# 04_RV1126B_Core_Board.net
KiCad netlist of a schematic drawn in Altium Designer
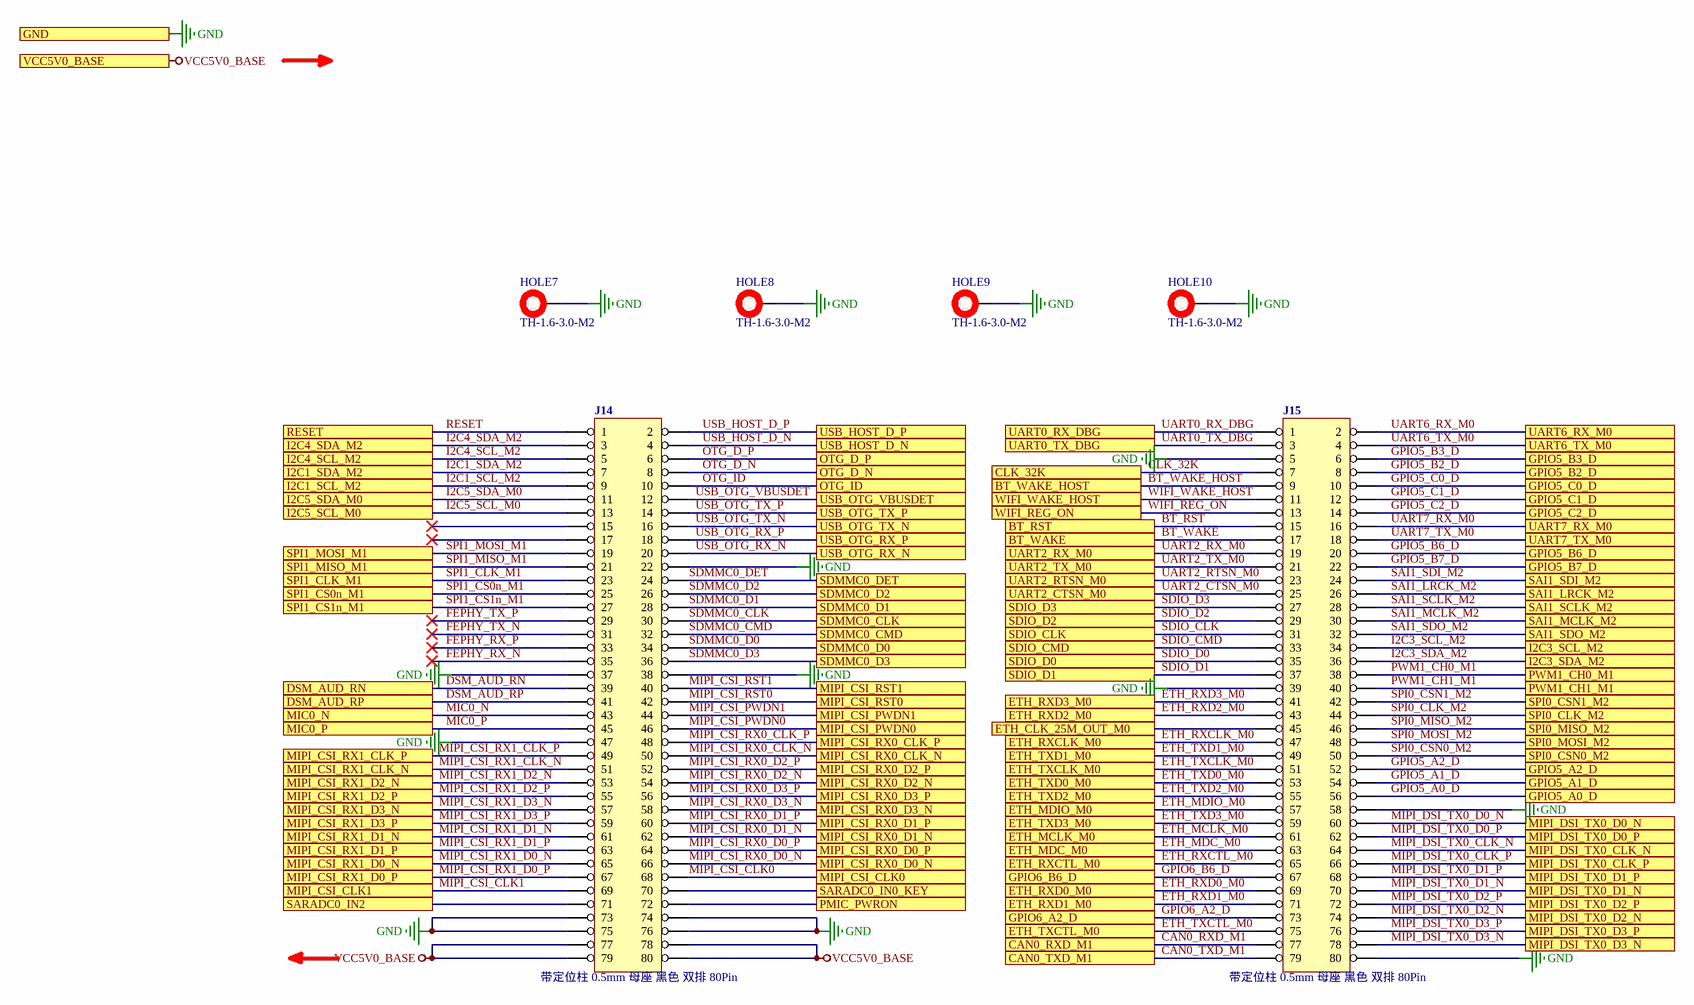
[diagram p0: 04.RV1126B_Core_Board.SchDoc]

(export (version "E")
  (design (tool "Eeschema 10.0.6"))
  (components
    (comp (ref "HOLE7")
      (value "TH-1.6-3.0-M2")
      (footprint "TH-1.6-3.0-M2")
      (description "SPZL000886")
      (fields (field (name "型号") "TH-1.6-3.0-M2"))
      (libsource (lib "Other_EASY-EAI") (part "螺柱 TH-1.6-3.0-M2"))
    )
    (comp (ref "HOLE8")
      (value "TH-1.6-3.0-M2")
      (footprint "TH-1.6-3.0-M2")
      (description "SPZL000886")
      (fields (field (name "型号") "TH-1.6-3.0-M2"))
      (libsource (lib "Other_EASY-EAI") (part "螺柱 TH-1.6-3.0-M2"))
    )
    (comp (ref "HOLE9")
      (value "TH-1.6-3.0-M2")
      (footprint "TH-1.6-3.0-M2")
      (description "SPZL000886")
      (fields (field (name "型号") "TH-1.6-3.0-M2"))
      (libsource (lib "Other_EASY-EAI") (part "螺柱 TH-1.6-3.0-M2"))
    )
    (comp (ref "HOLE10")
      (value "TH-1.6-3.0-M2")
      (footprint "TH-1.6-3.0-M2")
      (description "SPZL000886")
      (fields (field (name "型号") "TH-1.6-3.0-M2"))
      (libsource (lib "Other_EASY-EAI") (part "螺柱 TH-1.6-3.0-M2"))
    )
    (comp (ref "J14")
      (value "DF12NA(3.0)-80DP-0.5V(51)")
      (footprint "CONN-SMD_80P-P0.50_DF12NA-3.0-80DP-0.5V")
      (description "SPZL000772")
      (fields (field (name "描述") "带定位柱 0.5mm 母座 黑色 双排 80Pin"))
      (libsource (lib "Connector_EASY-EAI") (part "DF12NA(3.0)-80DP-0.5V(51)"))
    )
    (comp (ref "J15")
      (value "DF12NA(3.0)-80DP-0.5V(51)")
      (footprint "CONN-SMD_80P-P0.50_DF12NA-3.0-80DP-0.5V")
      (description "SPZL000772")
      (fields (field (name "描述") "带定位柱 0.5mm 母座 黑色 双排 80Pin"))
      (libsource (lib "Connector_EASY-EAI") (part "DF12NA(3.0)-80DP-0.5V(51)"))
    )
  )
  (nets
    (net (code "1") (name "/BT_RST") (class "Default")
      (node (ref "J15") (pin "15") (pinfunction "15_15") (pintype "passive"))
    )
    (net (code "2") (name "/BT_WAKE") (class "Default")
      (node (ref "J15") (pin "17") (pinfunction "17_17") (pintype "passive"))
    )
    (net (code "3") (name "/BT_WAKE_HOST") (class "Default")
      (node (ref "J15") (pin "9") (pinfunction "9_9") (pintype "passive"))
    )
    (net (code "4") (name "/CAN0_RXD_M1") (class "Default")
      (node (ref "J15") (pin "77") (pinfunction "77_77") (pintype "passive"))
    )
    (net (code "5") (name "/CAN0_TXD_M1") (class "Default")
      (node (ref "J15") (pin "79") (pinfunction "79_79") (pintype "passive"))
    )
    (net (code "6") (name "/CLK_32K") (class "Default")
      (node (ref "J15") (pin "7") (pinfunction "7_7") (pintype "passive"))
    )
    (net (code "7") (name "/DSM_AUD_RN") (class "Default")
      (node (ref "J14") (pin "39") (pinfunction "39_39") (pintype "passive"))
    )
    (net (code "8") (name "/DSM_AUD_RP") (class "Default")
      (node (ref "J14") (pin "41") (pinfunction "41_41") (pintype "passive"))
    )
    (net (code "9") (name "/ETH_CLK_25M_OUT_M0") (class "Default")
      (node (ref "J15") (pin "45") (pinfunction "45_45") (pintype "passive"))
    )
    (net (code "10") (name "/ETH_MCLK_M0") (class "Default")
      (node (ref "J15") (pin "61") (pinfunction "61_61") (pintype "passive"))
    )
    (net (code "11") (name "/ETH_MDC_M0") (class "Default")
      (node (ref "J15") (pin "63") (pinfunction "63_63") (pintype "passive"))
    )
    (net (code "12") (name "/ETH_MDIO_M0") (class "Default")
      (node (ref "J15") (pin "57") (pinfunction "57_57") (pintype "passive"))
    )
    (net (code "13") (name "/ETH_RXCLK_M0") (class "Default")
      (node (ref "J15") (pin "47") (pinfunction "47_47") (pintype "passive"))
    )
    (net (code "14") (name "/ETH_RXCTL_M0") (class "Default")
      (node (ref "J15") (pin "65") (pinfunction "65_65") (pintype "passive"))
    )
    (net (code "15") (name "/ETH_RXD0_M0") (class "Default")
      (node (ref "J15") (pin "69") (pinfunction "69_69") (pintype "passive"))
    )
    (net (code "16") (name "/ETH_RXD1_M0") (class "Default")
      (node (ref "J15") (pin "71") (pinfunction "71_71") (pintype "passive"))
    )
    (net (code "17") (name "/ETH_RXD2_M0") (class "Default")
      (node (ref "J15") (pin "43") (pinfunction "43_43") (pintype "passive"))
    )
    (net (code "18") (name "/ETH_RXD3_M0") (class "Default")
      (node (ref "J15") (pin "41") (pinfunction "41_41") (pintype "passive"))
    )
    (net (code "19") (name "/ETH_TXCLK_M0") (class "Default")
      (node (ref "J15") (pin "51") (pinfunction "51_51") (pintype "passive"))
    )
    (net (code "20") (name "/ETH_TXCTL_M0") (class "Default")
      (node (ref "J15") (pin "75") (pinfunction "75_75") (pintype "passive"))
    )
    (net (code "21") (name "/ETH_TXD0_M0") (class "Default")
      (node (ref "J15") (pin "53") (pinfunction "53_53") (pintype "passive"))
    )
    (net (code "22") (name "/ETH_TXD1_M0") (class "Default")
      (node (ref "J15") (pin "49") (pinfunction "49_49") (pintype "passive"))
    )
    (net (code "23") (name "/ETH_TXD2_M0") (class "Default")
      (node (ref "J15") (pin "55") (pinfunction "55_55") (pintype "passive"))
    )
    (net (code "24") (name "/ETH_TXD3_M0") (class "Default")
      (node (ref "J15") (pin "59") (pinfunction "59_59") (pintype "passive"))
    )
    (net (code "25") (name "/FEPHY_RX_N") (class "Default")
      (node (ref "J14") (pin "35") (pinfunction "35_35") (pintype "passive+no_connect"))
    )
    (net (code "26") (name "/FEPHY_RX_P") (class "Default")
      (node (ref "J14") (pin "33") (pinfunction "33_33") (pintype "passive+no_connect"))
    )
    (net (code "27") (name "/FEPHY_TX_N") (class "Default")
      (node (ref "J14") (pin "31") (pinfunction "31_31") (pintype "passive+no_connect"))
    )
    (net (code "28") (name "/FEPHY_TX_P") (class "Default")
      (node (ref "J14") (pin "29") (pinfunction "29_29") (pintype "passive+no_connect"))
    )
    (net (code "29") (name "/GPIO5_A0_D") (class "Default")
      (node (ref "J15") (pin "56") (pinfunction "56_56") (pintype "passive"))
    )
    (net (code "30") (name "/GPIO5_A1_D") (class "Default")
      (node (ref "J15") (pin "54") (pinfunction "54_54") (pintype "passive"))
    )
    (net (code "31") (name "/GPIO5_A2_D") (class "Default")
      (node (ref "J15") (pin "52") (pinfunction "52_52") (pintype "passive"))
    )
    (net (code "32") (name "/GPIO5_B2_D") (class "Default")
      (node (ref "J15") (pin "8") (pinfunction "8_8") (pintype "passive"))
    )
    (net (code "33") (name "/GPIO5_B3_D") (class "Default")
      (node (ref "J15") (pin "6") (pinfunction "6_6") (pintype "passive"))
    )
    (net (code "34") (name "/GPIO5_B6_D") (class "Default")
      (node (ref "J15") (pin "20") (pinfunction "20_20") (pintype "passive"))
    )
    (net (code "35") (name "/GPIO5_B7_D") (class "Default")
      (node (ref "J15") (pin "22") (pinfunction "22_22") (pintype "passive"))
    )
    (net (code "36") (name "/GPIO5_C0_D") (class "Default")
      (node (ref "J15") (pin "10") (pinfunction "10_10") (pintype "passive"))
    )
    (net (code "37") (name "/GPIO5_C1_D") (class "Default")
      (node (ref "J15") (pin "12") (pinfunction "12_12") (pintype "passive"))
    )
    (net (code "38") (name "/GPIO5_C2_D") (class "Default")
      (node (ref "J15") (pin "14") (pinfunction "14_14") (pintype "passive"))
    )
    (net (code "39") (name "/GPIO6_A2_D") (class "Default")
      (node (ref "J15") (pin "73") (pinfunction "73_73") (pintype "passive"))
    )
    (net (code "40") (name "/GPIO6_B6_D") (class "Default")
      (node (ref "J15") (pin "67") (pinfunction "67_67") (pintype "passive"))
    )
    (net (code "41") (name "/I2C1_SCL_M2") (class "Default")
      (node (ref "J14") (pin "9") (pinfunction "9_9") (pintype "passive"))
    )
    (net (code "42") (name "/I2C1_SDA_M2") (class "Default")
      (node (ref "J14") (pin "7") (pinfunction "7_7") (pintype "passive"))
    )
    (net (code "43") (name "/I2C3_SCL_M2") (class "Default")
      (node (ref "J15") (pin "34") (pinfunction "34_34") (pintype "passive"))
    )
    (net (code "44") (name "/I2C3_SDA_M2") (class "Default")
      (node (ref "J15") (pin "36") (pinfunction "36_36") (pintype "passive"))
    )
    (net (code "45") (name "/I2C4_SCL_M2") (class "Default")
      (node (ref "J14") (pin "5") (pinfunction "5_5") (pintype "passive"))
    )
    (net (code "46") (name "/I2C4_SDA_M2") (class "Default")
      (node (ref "J14") (pin "3") (pinfunction "3_3") (pintype "passive"))
    )
    (net (code "47") (name "/I2C5_SCL_M0") (class "Default")
      (node (ref "J14") (pin "13") (pinfunction "13_13") (pintype "passive"))
    )
    (net (code "48") (name "/I2C5_SDA_M0") (class "Default")
      (node (ref "J14") (pin "11") (pinfunction "11_11") (pintype "passive"))
    )
    (net (code "49") (name "/MIC0_N") (class "Default")
      (node (ref "J14") (pin "43") (pinfunction "43_43") (pintype "passive"))
    )
    (net (code "50") (name "/MIC0_P") (class "Default")
      (node (ref "J14") (pin "45") (pinfunction "45_45") (pintype "passive"))
    )
    (net (code "51") (name "/MIPI_CSI_CLK0") (class "Default")
      (node (ref "J14") (pin "68") (pinfunction "68_68") (pintype "passive"))
    )
    (net (code "52") (name "/MIPI_CSI_CLK1") (class "Default")
      (node (ref "J14") (pin "69") (pinfunction "69_69") (pintype "passive"))
    )
    (net (code "53") (name "/MIPI_CSI_PWDN0") (class "Default")
      (node (ref "J14") (pin "46") (pinfunction "46_46") (pintype "passive"))
    )
    (net (code "54") (name "/MIPI_CSI_PWDN1") (class "Default")
      (node (ref "J14") (pin "44") (pinfunction "44_44") (pintype "passive"))
    )
    (net (code "55") (name "/MIPI_CSI_RST0") (class "Default")
      (node (ref "J14") (pin "42") (pinfunction "42_42") (pintype "passive"))
    )
    (net (code "56") (name "/MIPI_CSI_RST1") (class "Default")
      (node (ref "J14") (pin "40") (pinfunction "40_40") (pintype "passive"))
    )
    (net (code "57") (name "/MIPI_CSI_RX0_CLK_N") (class "Default")
      (node (ref "J14") (pin "50") (pinfunction "50_50") (pintype "passive"))
    )
    (net (code "58") (name "/MIPI_CSI_RX0_CLK_P") (class "Default")
      (node (ref "J14") (pin "48") (pinfunction "48_48") (pintype "passive"))
    )
    (net (code "59") (name "/MIPI_CSI_RX0_D0_N") (class "Default")
      (node (ref "J14") (pin "66") (pinfunction "66_66") (pintype "passive"))
    )
    (net (code "60") (name "/MIPI_CSI_RX0_D0_P") (class "Default")
      (node (ref "J14") (pin "64") (pinfunction "64_64") (pintype "passive"))
    )
    (net (code "61") (name "/MIPI_CSI_RX0_D1_N") (class "Default")
      (node (ref "J14") (pin "62") (pinfunction "62_62") (pintype "passive"))
    )
    (net (code "62") (name "/MIPI_CSI_RX0_D1_P") (class "Default")
      (node (ref "J14") (pin "60") (pinfunction "60_60") (pintype "passive"))
    )
    (net (code "63") (name "/MIPI_CSI_RX0_D2_N") (class "Default")
      (node (ref "J14") (pin "54") (pinfunction "54_54") (pintype "passive"))
    )
    (net (code "64") (name "/MIPI_CSI_RX0_D2_P") (class "Default")
      (node (ref "J14") (pin "52") (pinfunction "52_52") (pintype "passive"))
    )
    (net (code "65") (name "/MIPI_CSI_RX0_D3_N") (class "Default")
      (node (ref "J14") (pin "58") (pinfunction "58_58") (pintype "passive"))
    )
    (net (code "66") (name "/MIPI_CSI_RX0_D3_P") (class "Default")
      (node (ref "J14") (pin "56") (pinfunction "56_56") (pintype "passive"))
    )
    (net (code "67") (name "/MIPI_CSI_RX1_CLK_N") (class "Default")
      (node (ref "J14") (pin "51") (pinfunction "51_51") (pintype "passive"))
    )
    (net (code "68") (name "/MIPI_CSI_RX1_CLK_P") (class "Default")
      (node (ref "J14") (pin "49") (pinfunction "49_49") (pintype "passive"))
    )
    (net (code "69") (name "/MIPI_CSI_RX1_D0_N") (class "Default")
      (node (ref "J14") (pin "65") (pinfunction "65_65") (pintype "passive"))
    )
    (net (code "70") (name "/MIPI_CSI_RX1_D0_P") (class "Default")
      (node (ref "J14") (pin "67") (pinfunction "67_67") (pintype "passive"))
    )
    (net (code "71") (name "/MIPI_CSI_RX1_D1_N") (class "Default")
      (node (ref "J14") (pin "61") (pinfunction "61_61") (pintype "passive"))
    )
    (net (code "72") (name "/MIPI_CSI_RX1_D1_P") (class "Default")
      (node (ref "J14") (pin "63") (pinfunction "63_63") (pintype "passive"))
    )
    (net (code "73") (name "/MIPI_CSI_RX1_D2_N") (class "Default")
      (node (ref "J14") (pin "53") (pinfunction "53_53") (pintype "passive"))
    )
    (net (code "74") (name "/MIPI_CSI_RX1_D2_P") (class "Default")
      (node (ref "J14") (pin "55") (pinfunction "55_55") (pintype "passive"))
    )
    (net (code "75") (name "/MIPI_CSI_RX1_D3_N") (class "Default")
      (node (ref "J14") (pin "57") (pinfunction "57_57") (pintype "passive"))
    )
    (net (code "76") (name "/MIPI_CSI_RX1_D3_P") (class "Default")
      (node (ref "J14") (pin "59") (pinfunction "59_59") (pintype "passive"))
    )
    (net (code "77") (name "/MIPI_DSI_TX0_CLK_N") (class "Default")
      (node (ref "J15") (pin "64") (pinfunction "64_64") (pintype "passive"))
    )
    (net (code "78") (name "/MIPI_DSI_TX0_CLK_P") (class "Default")
      (node (ref "J15") (pin "66") (pinfunction "66_66") (pintype "passive"))
    )
    (net (code "79") (name "/MIPI_DSI_TX0_D0_N") (class "Default")
      (node (ref "J15") (pin "60") (pinfunction "60_60") (pintype "passive"))
    )
    (net (code "80") (name "/MIPI_DSI_TX0_D0_P") (class "Default")
      (node (ref "J15") (pin "62") (pinfunction "62_62") (pintype "passive"))
    )
    (net (code "81") (name "/MIPI_DSI_TX0_D1_N") (class "Default")
      (node (ref "J15") (pin "70") (pinfunction "70_70") (pintype "passive"))
    )
    (net (code "82") (name "/MIPI_DSI_TX0_D1_P") (class "Default")
      (node (ref "J15") (pin "68") (pinfunction "68_68") (pintype "passive"))
    )
    (net (code "83") (name "/MIPI_DSI_TX0_D2_N") (class "Default")
      (node (ref "J15") (pin "74") (pinfunction "74_74") (pintype "passive"))
    )
    (net (code "84") (name "/MIPI_DSI_TX0_D2_P") (class "Default")
      (node (ref "J15") (pin "72") (pinfunction "72_72") (pintype "passive"))
    )
    (net (code "85") (name "/MIPI_DSI_TX0_D3_N") (class "Default")
      (node (ref "J15") (pin "78") (pinfunction "78_78") (pintype "passive"))
    )
    (net (code "86") (name "/MIPI_DSI_TX0_D3_P") (class "Default")
      (node (ref "J15") (pin "76") (pinfunction "76_76") (pintype "passive"))
    )
    (net (code "87") (name "/OTG_D_N") (class "Default")
      (node (ref "J14") (pin "8") (pinfunction "8_8") (pintype "passive"))
    )
    (net (code "88") (name "/OTG_D_P") (class "Default")
      (node (ref "J14") (pin "6") (pinfunction "6_6") (pintype "passive"))
    )
    (net (code "89") (name "/OTG_ID") (class "Default")
      (node (ref "J14") (pin "10") (pinfunction "10_10") (pintype "passive"))
    )
    (net (code "90") (name "/PMIC_PWRON") (class "Default")
      (node (ref "J14") (pin "72") (pinfunction "72_72") (pintype "passive"))
    )
    (net (code "91") (name "/PWM1_CH0_M1") (class "Default")
      (node (ref "J15") (pin "38") (pinfunction "38_38") (pintype "passive"))
    )
    (net (code "92") (name "/PWM1_CH1_M1") (class "Default")
      (node (ref "J15") (pin "40") (pinfunction "40_40") (pintype "passive"))
    )
    (net (code "93") (name "/RESET") (class "Default")
      (node (ref "J14") (pin "1") (pinfunction "1_1") (pintype "passive"))
    )
    (net (code "94") (name "/SAI1_LRCK_M2") (class "Default")
      (node (ref "J15") (pin "26") (pinfunction "26_26") (pintype "passive"))
    )
    (net (code "95") (name "/SAI1_MCLK_M2") (class "Default")
      (node (ref "J15") (pin "30") (pinfunction "30_30") (pintype "passive"))
    )
    (net (code "96") (name "/SAI1_SCLK_M2") (class "Default")
      (node (ref "J15") (pin "28") (pinfunction "28_28") (pintype "passive"))
    )
    (net (code "97") (name "/SAI1_SDI_M2") (class "Default")
      (node (ref "J15") (pin "24") (pinfunction "24_24") (pintype "passive"))
    )
    (net (code "98") (name "/SAI1_SDO_M2") (class "Default")
      (node (ref "J15") (pin "32") (pinfunction "32_32") (pintype "passive"))
    )
    (net (code "99") (name "/SARADC0_IN0_KEY") (class "Default")
      (node (ref "J14") (pin "70") (pinfunction "70_70") (pintype "passive"))
    )
    (net (code "100") (name "/SARADC0_IN2") (class "Default")
      (node (ref "J14") (pin "71") (pinfunction "71_71") (pintype "passive"))
    )
    (net (code "101") (name "/SDIO_CLK") (class "Default")
      (node (ref "J15") (pin "31") (pinfunction "31_31") (pintype "passive"))
    )
    (net (code "102") (name "/SDIO_CMD") (class "Default")
      (node (ref "J15") (pin "33") (pinfunction "33_33") (pintype "passive"))
    )
    (net (code "103") (name "/SDIO_D0") (class "Default")
      (node (ref "J15") (pin "35") (pinfunction "35_35") (pintype "passive"))
    )
    (net (code "104") (name "/SDIO_D1") (class "Default")
      (node (ref "J15") (pin "37") (pinfunction "37_37") (pintype "passive"))
    )
    (net (code "105") (name "/SDIO_D2") (class "Default")
      (node (ref "J15") (pin "29") (pinfunction "29_29") (pintype "passive"))
    )
    (net (code "106") (name "/SDIO_D3") (class "Default")
      (node (ref "J15") (pin "27") (pinfunction "27_27") (pintype "passive"))
    )
    (net (code "107") (name "/SDMMC0_CLK") (class "Default")
      (node (ref "J14") (pin "30") (pinfunction "30_30") (pintype "passive"))
    )
    (net (code "108") (name "/SDMMC0_CMD") (class "Default")
      (node (ref "J14") (pin "32") (pinfunction "32_32") (pintype "passive"))
    )
    (net (code "109") (name "/SDMMC0_D0") (class "Default")
      (node (ref "J14") (pin "34") (pinfunction "34_34") (pintype "passive"))
    )
    (net (code "110") (name "/SDMMC0_D1") (class "Default")
      (node (ref "J14") (pin "28") (pinfunction "28_28") (pintype "passive"))
    )
    (net (code "111") (name "/SDMMC0_D2") (class "Default")
      (node (ref "J14") (pin "26") (pinfunction "26_26") (pintype "passive"))
    )
    (net (code "112") (name "/SDMMC0_D3") (class "Default")
      (node (ref "J14") (pin "36") (pinfunction "36_36") (pintype "passive"))
    )
    (net (code "113") (name "/SDMMC0_DET") (class "Default")
      (node (ref "J14") (pin "24") (pinfunction "24_24") (pintype "passive"))
    )
    (net (code "114") (name "/SPI0_CLK_M2") (class "Default")
      (node (ref "J15") (pin "44") (pinfunction "44_44") (pintype "passive"))
    )
    (net (code "115") (name "/SPI0_CSN0_M2") (class "Default")
      (node (ref "J15") (pin "50") (pinfunction "50_50") (pintype "passive"))
    )
    (net (code "116") (name "/SPI0_CSN1_M2") (class "Default")
      (node (ref "J15") (pin "42") (pinfunction "42_42") (pintype "passive"))
    )
    (net (code "117") (name "/SPI0_MISO_M2") (class "Default")
      (node (ref "J15") (pin "46") (pinfunction "46_46") (pintype "passive"))
    )
    (net (code "118") (name "/SPI0_MOSI_M2") (class "Default")
      (node (ref "J15") (pin "48") (pinfunction "48_48") (pintype "passive"))
    )
    (net (code "119") (name "/SPI1_CLK_M1") (class "Default")
      (node (ref "J14") (pin "23") (pinfunction "23_23") (pintype "passive"))
    )
    (net (code "120") (name "/SPI1_CS0n_M1") (class "Default")
      (node (ref "J14") (pin "25") (pinfunction "25_25") (pintype "passive"))
    )
    (net (code "121") (name "/SPI1_CS1n_M1") (class "Default")
      (node (ref "J14") (pin "27") (pinfunction "27_27") (pintype "passive"))
    )
    (net (code "122") (name "/SPI1_MISO_M1") (class "Default")
      (node (ref "J14") (pin "21") (pinfunction "21_21") (pintype "passive"))
    )
    (net (code "123") (name "/SPI1_MOSI_M1") (class "Default")
      (node (ref "J14") (pin "19") (pinfunction "19_19") (pintype "passive"))
    )
    (net (code "124") (name "/UART0_RX_DBG") (class "Default")
      (node (ref "J15") (pin "1") (pinfunction "1_1") (pintype "passive"))
    )
    (net (code "125") (name "/UART0_TX_DBG") (class "Default")
      (node (ref "J15") (pin "3") (pinfunction "3_3") (pintype "passive"))
    )
    (net (code "126") (name "/UART2_CTSN_M0") (class "Default")
      (node (ref "J15") (pin "25") (pinfunction "25_25") (pintype "passive"))
    )
    (net (code "127") (name "/UART2_RTSN_M0") (class "Default")
      (node (ref "J15") (pin "23") (pinfunction "23_23") (pintype "passive"))
    )
    (net (code "128") (name "/UART2_RX_M0") (class "Default")
      (node (ref "J15") (pin "19") (pinfunction "19_19") (pintype "passive"))
    )
    (net (code "129") (name "/UART2_TX_M0") (class "Default")
      (node (ref "J15") (pin "21") (pinfunction "21_21") (pintype "passive"))
    )
    (net (code "130") (name "/UART6_RX_M0") (class "Default")
      (node (ref "J15") (pin "2") (pinfunction "2_2") (pintype "passive"))
    )
    (net (code "131") (name "/UART6_TX_M0") (class "Default")
      (node (ref "J15") (pin "4") (pinfunction "4_4") (pintype "passive"))
    )
    (net (code "132") (name "/UART7_RX_M0") (class "Default")
      (node (ref "J15") (pin "16") (pinfunction "16_16") (pintype "passive"))
    )
    (net (code "133") (name "/UART7_TX_M0") (class "Default")
      (node (ref "J15") (pin "18") (pinfunction "18_18") (pintype "passive"))
    )
    (net (code "134") (name "/USB_HOST_D_N") (class "Default")
      (node (ref "J14") (pin "4") (pinfunction "4_4") (pintype "passive"))
    )
    (net (code "135") (name "/USB_HOST_D_P") (class "Default")
      (node (ref "J14") (pin "2") (pinfunction "2_2") (pintype "passive"))
    )
    (net (code "136") (name "/USB_OTG_RX_N") (class "Default")
      (node (ref "J14") (pin "20") (pinfunction "20_20") (pintype "passive"))
    )
    (net (code "137") (name "/USB_OTG_RX_P") (class "Default")
      (node (ref "J14") (pin "18") (pinfunction "18_18") (pintype "passive"))
    )
    (net (code "138") (name "/USB_OTG_TX_N") (class "Default")
      (node (ref "J14") (pin "16") (pinfunction "16_16") (pintype "passive"))
    )
    (net (code "139") (name "/USB_OTG_TX_P") (class "Default")
      (node (ref "J14") (pin "14") (pinfunction "14_14") (pintype "passive"))
    )
    (net (code "140") (name "/USB_OTG_VBUSDET") (class "Default")
      (node (ref "J14") (pin "12") (pinfunction "12_12") (pintype "passive"))
    )
    (net (code "141") (name "/WIFI_REG_ON") (class "Default")
      (node (ref "J15") (pin "13") (pinfunction "13_13") (pintype "passive"))
    )
    (net (code "142") (name "/WIFI_WAKE_HOST") (class "Default")
      (node (ref "J15") (pin "11") (pinfunction "11_11") (pintype "passive"))
    )
    (net (code "143") (name "GND") (class "Default")
      (node (ref "HOLE10") (pin "1") (pintype "passive"))
      (node (ref "HOLE7") (pin "1") (pintype "passive"))
      (node (ref "HOLE8") (pin "1") (pintype "passive"))
      (node (ref "HOLE9") (pin "1") (pintype "passive"))
      (node (ref "J14") (pin "22") (pinfunction "22_22") (pintype "passive"))
      (node (ref "J14") (pin "37") (pinfunction "37_37") (pintype "passive"))
      (node (ref "J14") (pin "38") (pinfunction "38_38") (pintype "passive"))
      (node (ref "J14") (pin "47") (pinfunction "47_47") (pintype "passive"))
      (node (ref "J14") (pin "73") (pinfunction "73_73") (pintype "passive"))
      (node (ref "J14") (pin "74") (pinfunction "74_74") (pintype "passive"))
      (node (ref "J14") (pin "75") (pinfunction "75_75") (pintype "passive"))
      (node (ref "J14") (pin "76") (pinfunction "76_76") (pintype "passive"))
      (node (ref "J15") (pin "39") (pinfunction "39_39") (pintype "passive"))
      (node (ref "J15") (pin "5") (pinfunction "5_5") (pintype "passive"))
      (node (ref "J15") (pin "58") (pinfunction "58_58") (pintype "passive"))
      (node (ref "J15") (pin "80") (pinfunction "80_80") (pintype "passive"))
    )
    (net (code "144") (name "VCC5V0_BASE") (class "Default")
      (node (ref "J14") (pin "77") (pinfunction "77_77") (pintype "passive"))
      (node (ref "J14") (pin "78") (pinfunction "78_78") (pintype "passive"))
      (node (ref "J14") (pin "79") (pinfunction "79_79") (pintype "passive"))
      (node (ref "J14") (pin "80") (pinfunction "80_80") (pintype "passive"))
    )
    (net (code "145") (name "unconnected-(J14-Pad15)") (class "Default")
      (node (ref "J14") (pin "15") (pinfunction "15_15") (pintype "passive+no_connect"))
    )
    (net (code "146") (name "unconnected-(J14-Pad17)") (class "Default")
      (node (ref "J14") (pin "17") (pinfunction "17_17") (pintype "passive+no_connect"))
    )
  )
)
